# XL4432-SMT4.net
KiCad netlist of a schematic drawn in EAGLE
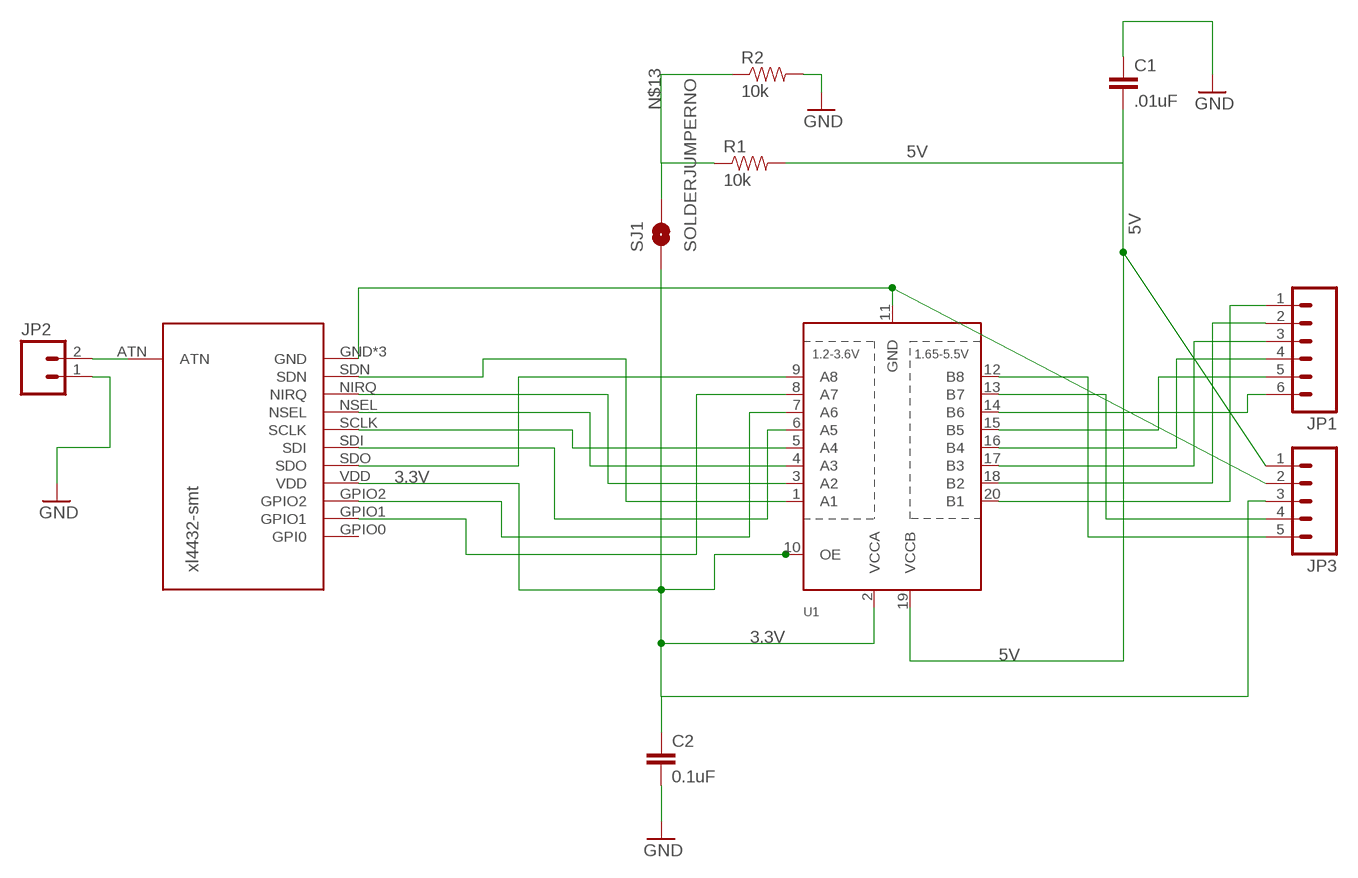
[diagram p0: schematic, sheet 1]

(export (version "E")
  (design (tool "Eeschema 10.0.6"))
  (components
    (comp (ref "C1")
      (value ".01uF")
      (footprint "eagle-import:0805")
      (libsource (lib "eagle-import") (part "CAP0805"))
    )
    (comp (ref "C2")
      (value "0.1uF")
      (footprint "eagle-import:0805")
      (libsource (lib "eagle-import") (part "CAP0805"))
    )
    (comp (ref "JP1")
      (value "M06LOCK")
      (footprint "eagle-import:1X06_LOCK")
      (libsource (lib "eagle-import") (part "M06LOCK"))
    )
    (comp (ref "JP2")
      (value "M02LOCK")
      (footprint "eagle-import:1X02_LOCK")
      (libsource (lib "eagle-import") (part "M02LOCK"))
    )
    (comp (ref "JP3")
      (value "M05LOCK")
      (footprint "eagle-import:1X05_LOCK")
      (libsource (lib "eagle-import") (part "M05LOCK"))
    )
    (comp (ref "R1")
      (value "10k")
      (footprint "eagle-import:0805")
      (libsource (lib "eagle-import") (part "RESISTOR0805-RES"))
    )
    (comp (ref "R2")
      (value "10k")
      (footprint "eagle-import:0805")
      (libsource (lib "eagle-import") (part "RESISTOR0805-RES"))
    )
    (comp (ref "SJ1")
      (value "SOLDERJUMPERNO")
      (footprint "eagle-import:SJ_2S-NO")
      (libsource (lib "eagle-import") (part "SOLDERJUMPERNO"))
    )
    (comp (ref "U$1")
      (value "XL4432-SMT")
      (footprint "eagle-import:XL4432-SMT")
      (libsource (lib "eagle-import") (part "XL4432-SMT"))
    )
    (comp (ref "U1")
      (value "TXB0108PWR")
      (footprint "eagle-import:TSSOP20")
      (libsource (lib "eagle-import") (part "TXB0108PWR"))
    )
  )
  (nets
    (net (code "1") (name "/3.3V") (class "Default")
      (node (ref "C2") (pin "1") (pinfunction "1_1") (pintype "passive"))
      (node (ref "JP3") (pin "3") (pinfunction "3_3") (pintype "passive"))
      (node (ref "SJ1") (pin "1") (pinfunction "1_1") (pintype "passive"))
      (node (ref "U$1") (pin "VDD") (pinfunction "VDD_VDD") (pintype "bidirectional"))
      (node (ref "U1") (pin "10") (pinfunction "OE_10") (pintype "bidirectional"))
      (node (ref "U1") (pin "2") (pinfunction "VCCA_2") (pintype "bidirectional"))
    )
    (net (code "2") (name "/5V") (class "Default")
      (node (ref "C1") (pin "2") (pinfunction "2_2") (pintype "passive"))
      (node (ref "JP3") (pin "1") (pinfunction "1_1") (pintype "passive"))
      (node (ref "R1") (pin "2") (pinfunction "2_2") (pintype "passive"))
      (node (ref "U1") (pin "19") (pinfunction "VCCB_19") (pintype "bidirectional"))
    )
    (net (code "3") (name "/N$13") (class "Default")
      (node (ref "R1") (pin "1") (pinfunction "1_1") (pintype "passive"))
      (node (ref "R2") (pin "1") (pinfunction "1_1") (pintype "passive"))
      (node (ref "SJ1") (pin "2") (pinfunction "2_2") (pintype "passive"))
    )
    (net (code "4") (name "GND") (class "Default")
      (node (ref "C1") (pin "1") (pinfunction "1_1") (pintype "passive"))
      (node (ref "C2") (pin "2") (pinfunction "2_2") (pintype "passive"))
      (node (ref "JP2") (pin "1") (pinfunction "1_1") (pintype "passive"))
      (node (ref "JP3") (pin "2") (pinfunction "2_2") (pintype "passive"))
      (node (ref "R2") (pin "2") (pinfunction "2_2") (pintype "passive"))
      (node (ref "U$1") (pin "GND") (pinfunction "GND_GND") (pintype "bidirectional"))
      (node (ref "U$1") (pin "GND1") (pinfunction "GND_GND1") (pintype "bidirectional"))
      (node (ref "U$1") (pin "GND3") (pinfunction "GND_GND3") (pintype "bidirectional"))
      (node (ref "U1") (pin "11") (pinfunction "GND_11") (pintype "bidirectional"))
    )
    (net (code "5") (name "Net-(JP2-Pad2)") (class "Default")
      (node (ref "JP2") (pin "2") (pinfunction "2_2") (pintype "passive"))
      (node (ref "U$1") (pin "ATN") (pinfunction "ATN_ATN") (pintype "bidirectional"))
    )
    (net (code "6") (name "Net-(U1-A1)") (class "Default")
      (node (ref "U$1") (pin "SDN") (pinfunction "SDN_SDN") (pintype "bidirectional"))
      (node (ref "U1") (pin "1") (pinfunction "A1_1") (pintype "bidirectional"))
    )
    (net (code "7") (name "Net-(U1-A2)") (class "Default")
      (node (ref "U$1") (pin "NIRQ") (pinfunction "NIRQ_NIRQ") (pintype "bidirectional"))
      (node (ref "U1") (pin "3") (pinfunction "A2_3") (pintype "bidirectional"))
    )
    (net (code "8") (name "Net-(U1-A3)") (class "Default")
      (node (ref "U$1") (pin "NSEL") (pinfunction "NSEL_NSEL") (pintype "bidirectional"))
      (node (ref "U1") (pin "4") (pinfunction "A3_4") (pintype "bidirectional"))
    )
    (net (code "9") (name "Net-(U1-A4)") (class "Default")
      (node (ref "U$1") (pin "SCLK") (pinfunction "SCLK_SCLK") (pintype "bidirectional"))
      (node (ref "U1") (pin "5") (pinfunction "A4_5") (pintype "bidirectional"))
    )
    (net (code "10") (name "Net-(U1-A5)") (class "Default")
      (node (ref "U$1") (pin "SDI") (pinfunction "SDI_SDI") (pintype "bidirectional"))
      (node (ref "U1") (pin "6") (pinfunction "A5_6") (pintype "bidirectional"))
    )
    (net (code "11") (name "Net-(U1-A6)") (class "Default")
      (node (ref "U$1") (pin "GPIO2") (pinfunction "GPIO2_GPIO2") (pintype "bidirectional"))
      (node (ref "U1") (pin "7") (pinfunction "A6_7") (pintype "bidirectional"))
    )
    (net (code "12") (name "Net-(U1-A7)") (class "Default")
      (node (ref "U$1") (pin "GPIO1") (pinfunction "GPIO1_GPIO1") (pintype "bidirectional"))
      (node (ref "U1") (pin "8") (pinfunction "A7_8") (pintype "bidirectional"))
    )
    (net (code "13") (name "Net-(U1-A8)") (class "Default")
      (node (ref "U$1") (pin "SDO") (pinfunction "SDO_SDO") (pintype "bidirectional"))
      (node (ref "U1") (pin "9") (pinfunction "A8_9") (pintype "bidirectional"))
    )
    (net (code "14") (name "Net-(U1-B1)") (class "Default")
      (node (ref "JP1") (pin "1") (pinfunction "1_1") (pintype "passive"))
      (node (ref "U1") (pin "20") (pinfunction "B1_20") (pintype "bidirectional"))
    )
    (net (code "15") (name "Net-(U1-B2)") (class "Default")
      (node (ref "JP1") (pin "2") (pinfunction "2_2") (pintype "passive"))
      (node (ref "U1") (pin "18") (pinfunction "B2_18") (pintype "bidirectional"))
    )
    (net (code "16") (name "Net-(U1-B3)") (class "Default")
      (node (ref "JP1") (pin "3") (pinfunction "3_3") (pintype "passive"))
      (node (ref "U1") (pin "17") (pinfunction "B3_17") (pintype "bidirectional"))
    )
    (net (code "17") (name "Net-(U1-B4)") (class "Default")
      (node (ref "JP1") (pin "4") (pinfunction "4_4") (pintype "passive"))
      (node (ref "U1") (pin "16") (pinfunction "B4_16") (pintype "bidirectional"))
    )
    (net (code "18") (name "Net-(U1-B5)") (class "Default")
      (node (ref "JP1") (pin "5") (pinfunction "5_5") (pintype "passive"))
      (node (ref "U1") (pin "15") (pinfunction "B5_15") (pintype "bidirectional"))
    )
    (net (code "19") (name "Net-(U1-B6)") (class "Default")
      (node (ref "JP1") (pin "6") (pinfunction "6_6") (pintype "passive"))
      (node (ref "U1") (pin "14") (pinfunction "B6_14") (pintype "bidirectional"))
    )
    (net (code "20") (name "Net-(U1-B7)") (class "Default")
      (node (ref "JP3") (pin "4") (pinfunction "4_4") (pintype "passive"))
      (node (ref "U1") (pin "13") (pinfunction "B7_13") (pintype "bidirectional"))
    )
    (net (code "21") (name "Net-(U1-B8)") (class "Default")
      (node (ref "JP3") (pin "5") (pinfunction "5_5") (pintype "passive"))
      (node (ref "U1") (pin "12") (pinfunction "B8_12") (pintype "bidirectional"))
    )
    (net (code "22") (name "unconnected-(U$1-GPI0-PadGPIO0)") (class "Default")
      (node (ref "U$1") (pin "GPIO0") (pinfunction "GPI0_GPIO0") (pintype "bidirectional"))
    )
  )
)
